# SCH_angel-new-PCB-card_2025-01-17.net
KiCad netlist of a schematic drawn in EasyEDA
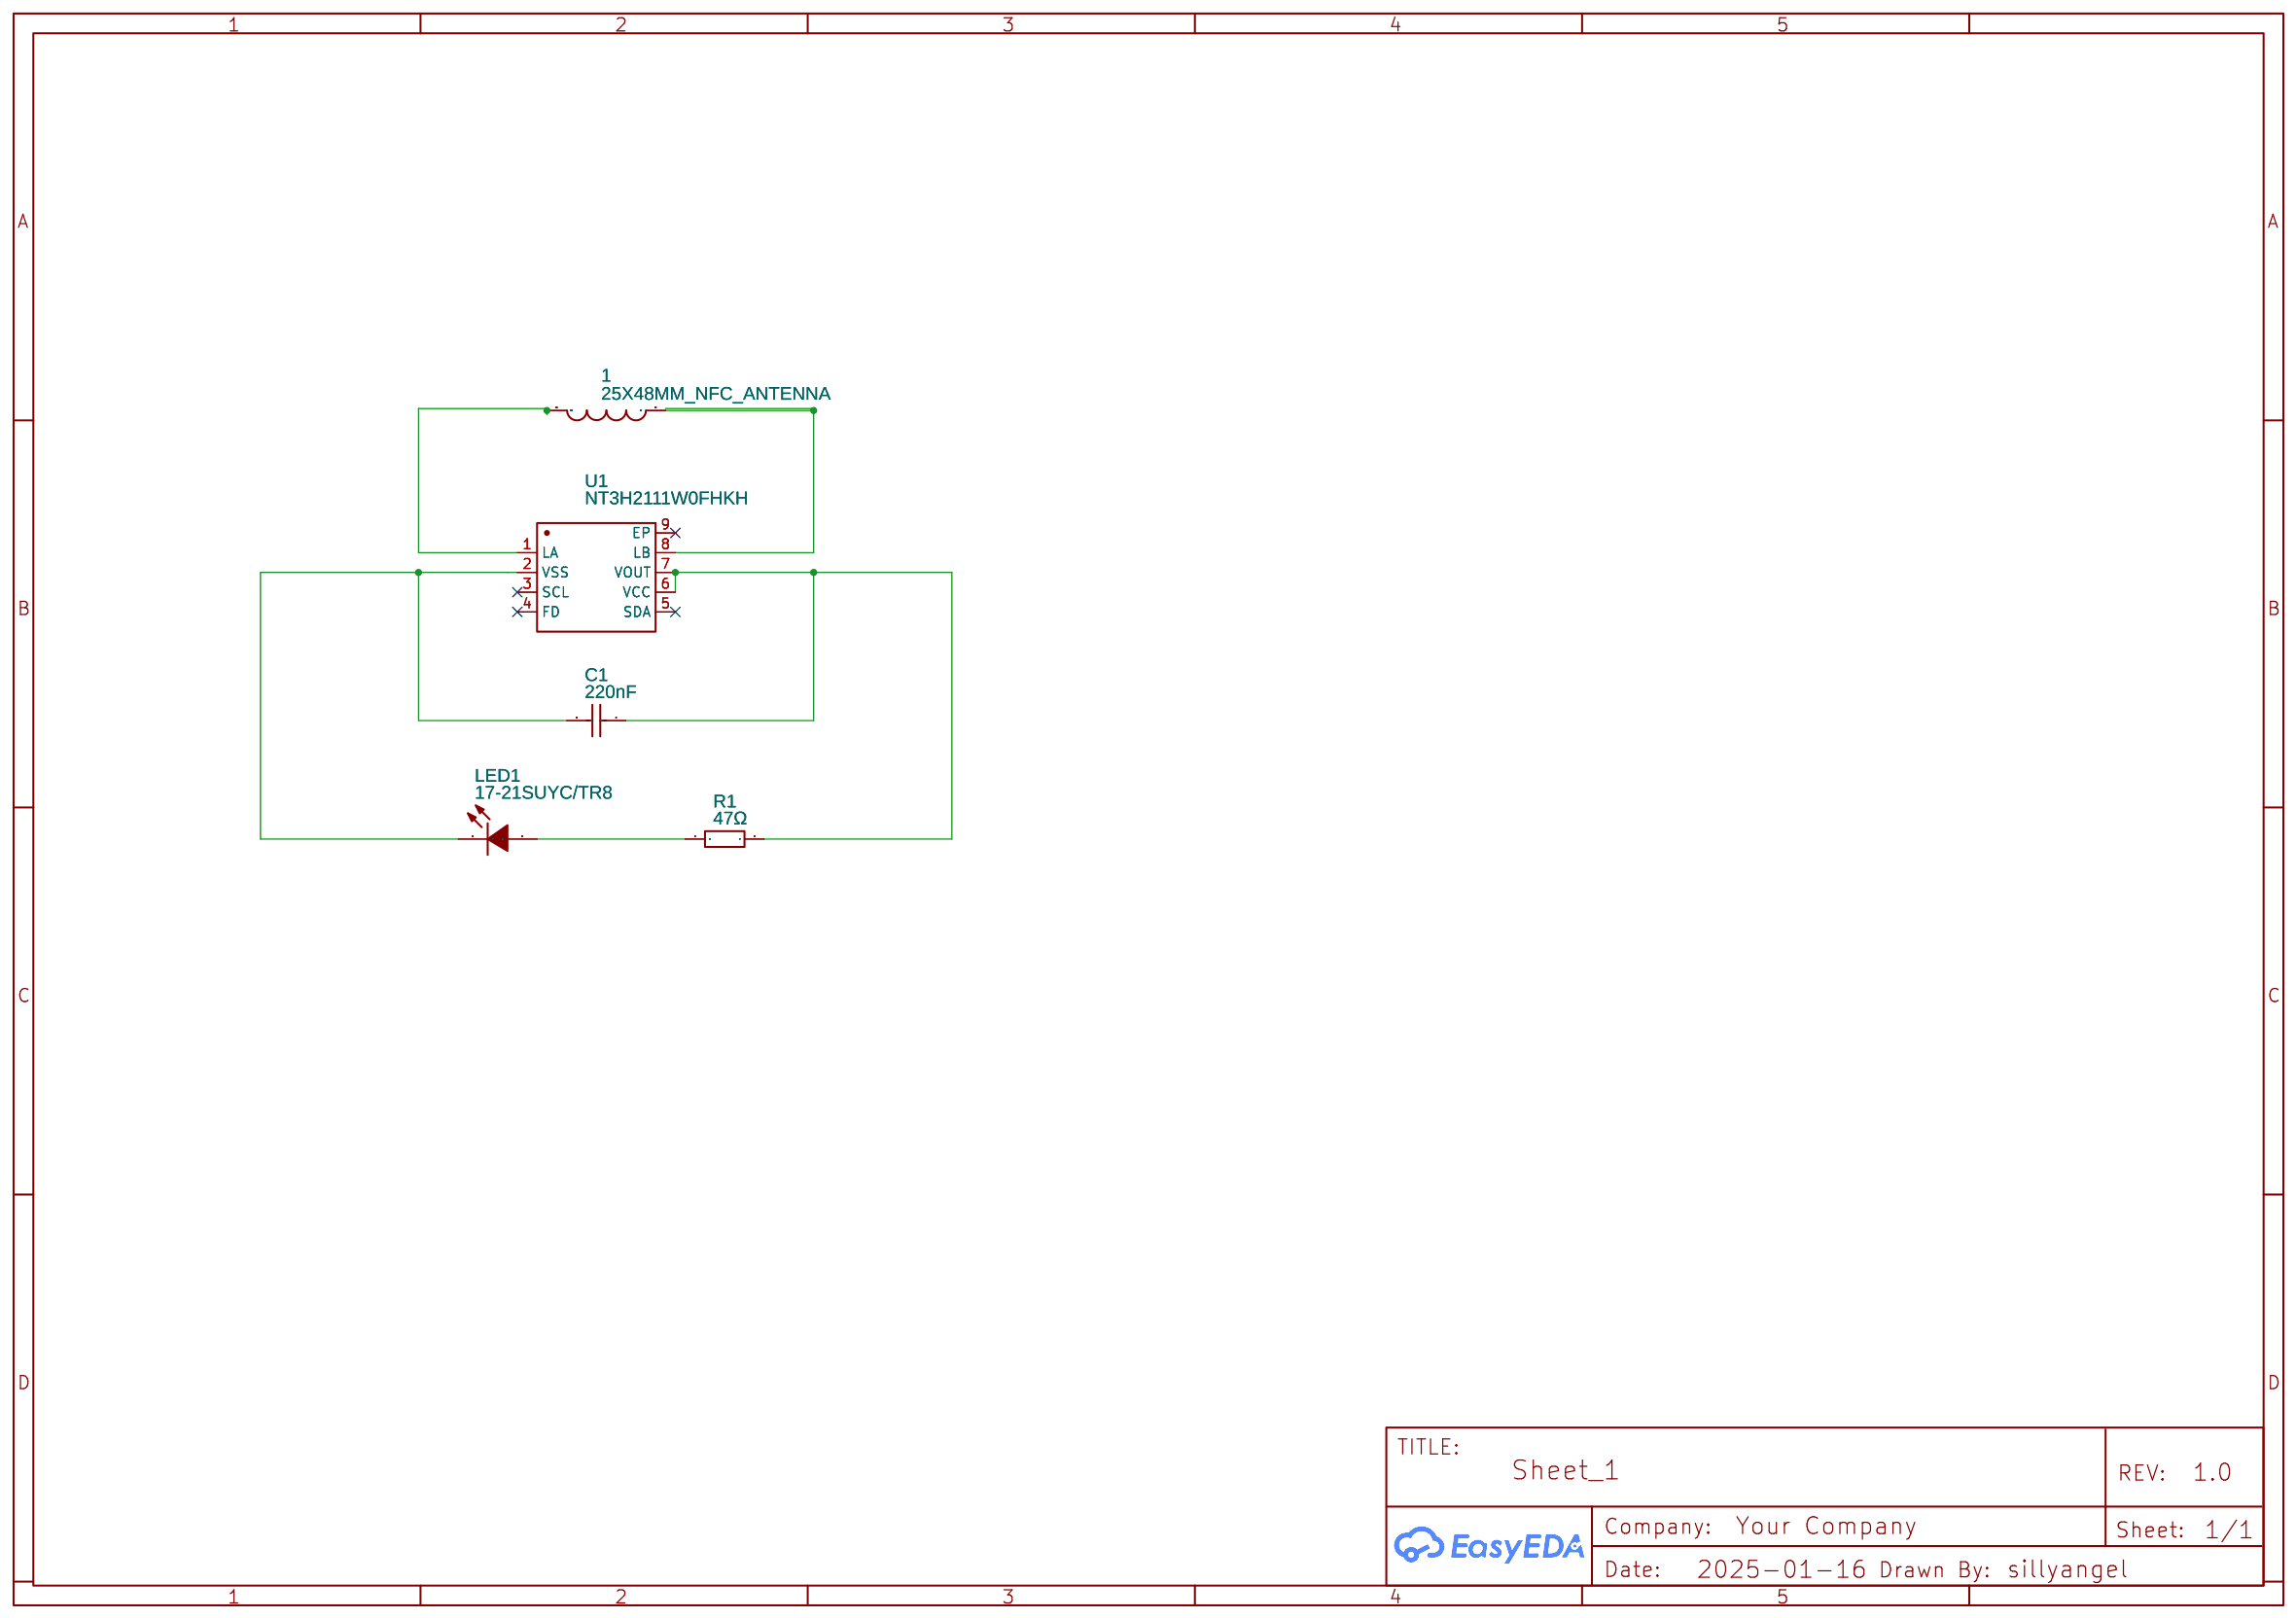
[diagram p0: schematic sheet]

(export (version "E")
  (design (tool "Eeschema 10.0.6"))
  (components
    (comp (ref "1") (value "25X48MM_NFC_ANTENNA") (libsource (lib "") (part "25X48MM_NFC_ANTENNA")))
    (comp (ref "C1")
      (value "220nF")
      (fields
        (field (name "Manufacturer Part") "CL10B224KA8NNNC")
        (field (name "Manufacturer") "SAMSUNG(三星)")
      )
      (libsource (lib "") (part "CL10B224KA8NNNC"))
    )
    (comp (ref "LED1")
      (value "17-21SUYC/TR8")
      (fields (field (name "Manufacturer Part") "KT-0805黄灯") (field (name "Manufacturer") "KENTO"))
      (libsource (lib "") (part "17-21SUYC/TR8"))
    )
    (comp (ref "R1")
      (value "47Ω")
      (fields
        (field (name "Manufacturer Part") "0603WAF470JT5E")
        (field (name "Manufacturer") "UNI-ROYAL(厚声)")
      )
      (libsource (lib "") (part "0603WAF470JT5E"))
    )
    (comp (ref "U1")
      (value "NT3H2111W0FHKH")
      (fields (field (name "Manufacturer") "NXP(恩智浦)"))
      (libsource (lib "") (part "NT3H2111W0FHKH"))
    )
  )
  (nets
    (net (code "1") (name "Net-(LED1-+)") (class "Default")
      (node (ref "LED1") (pin "1") (pinfunction "+_1") (pintype "unspecified"))
      (node (ref "R1") (pin "1") (pinfunction "1_1") (pintype "input"))
    )
    (net (code "2") (name "Net-(LED1--)") (class "Default")
      (node (ref "C1") (pin "1") (pinfunction "1_1") (pintype "input"))
      (node (ref "LED1") (pin "2") (pinfunction "-_2") (pintype "unspecified"))
      (node (ref "U1") (pin "2") (pinfunction "VSS_2") (pintype "unspecified"))
    )
    (net (code "3") (name "Net-(U1-LA)") (class "Default")
      (node (ref "1") (pin "P$2") (pinfunction "P$2_P$2") (pintype "bidirectional"))
      (node (ref "U1") (pin "1") (pinfunction "LA_1") (pintype "unspecified"))
    )
    (net (code "4") (name "Net-(U1-LB)") (class "Default")
      (node (ref "1") (pin "P$1") (pinfunction "P$1_P$1") (pintype "bidirectional"))
      (node (ref "U1") (pin "8") (pinfunction "LB_8") (pintype "unspecified"))
    )
    (net (code "5") (name "Net-(U1-VCC)") (class "Default")
      (node (ref "C1") (pin "2") (pinfunction "2_2") (pintype "input"))
      (node (ref "R1") (pin "2") (pinfunction "2_2") (pintype "input"))
      (node (ref "U1") (pin "6") (pinfunction "VCC_6") (pintype "unspecified"))
      (node (ref "U1") (pin "7") (pinfunction "VOUT_7") (pintype "unspecified"))
    )
    (net (code "6") (name "unconnected-(U1-EP-Pad9)") (class "Default")
      (node (ref "U1") (pin "9") (pinfunction "EP_9") (pintype "unspecified+no_connect"))
    )
    (net (code "7") (name "unconnected-(U1-FD-Pad4)") (class "Default")
      (node (ref "U1") (pin "4") (pinfunction "FD_4") (pintype "unspecified+no_connect"))
    )
    (net (code "8") (name "unconnected-(U1-SCL-Pad3)") (class "Default")
      (node (ref "U1") (pin "3") (pinfunction "SCL_3") (pintype "unspecified+no_connect"))
    )
    (net (code "9") (name "unconnected-(U1-SDA-Pad5)") (class "Default")
      (node (ref "U1") (pin "5") (pinfunction "SDA_5") (pintype "unspecified+no_connect"))
    )
  )
)
